# SCH_LED-CHASER_2025-11-11.net
KiCad netlist of a schematic drawn in EasyEDA
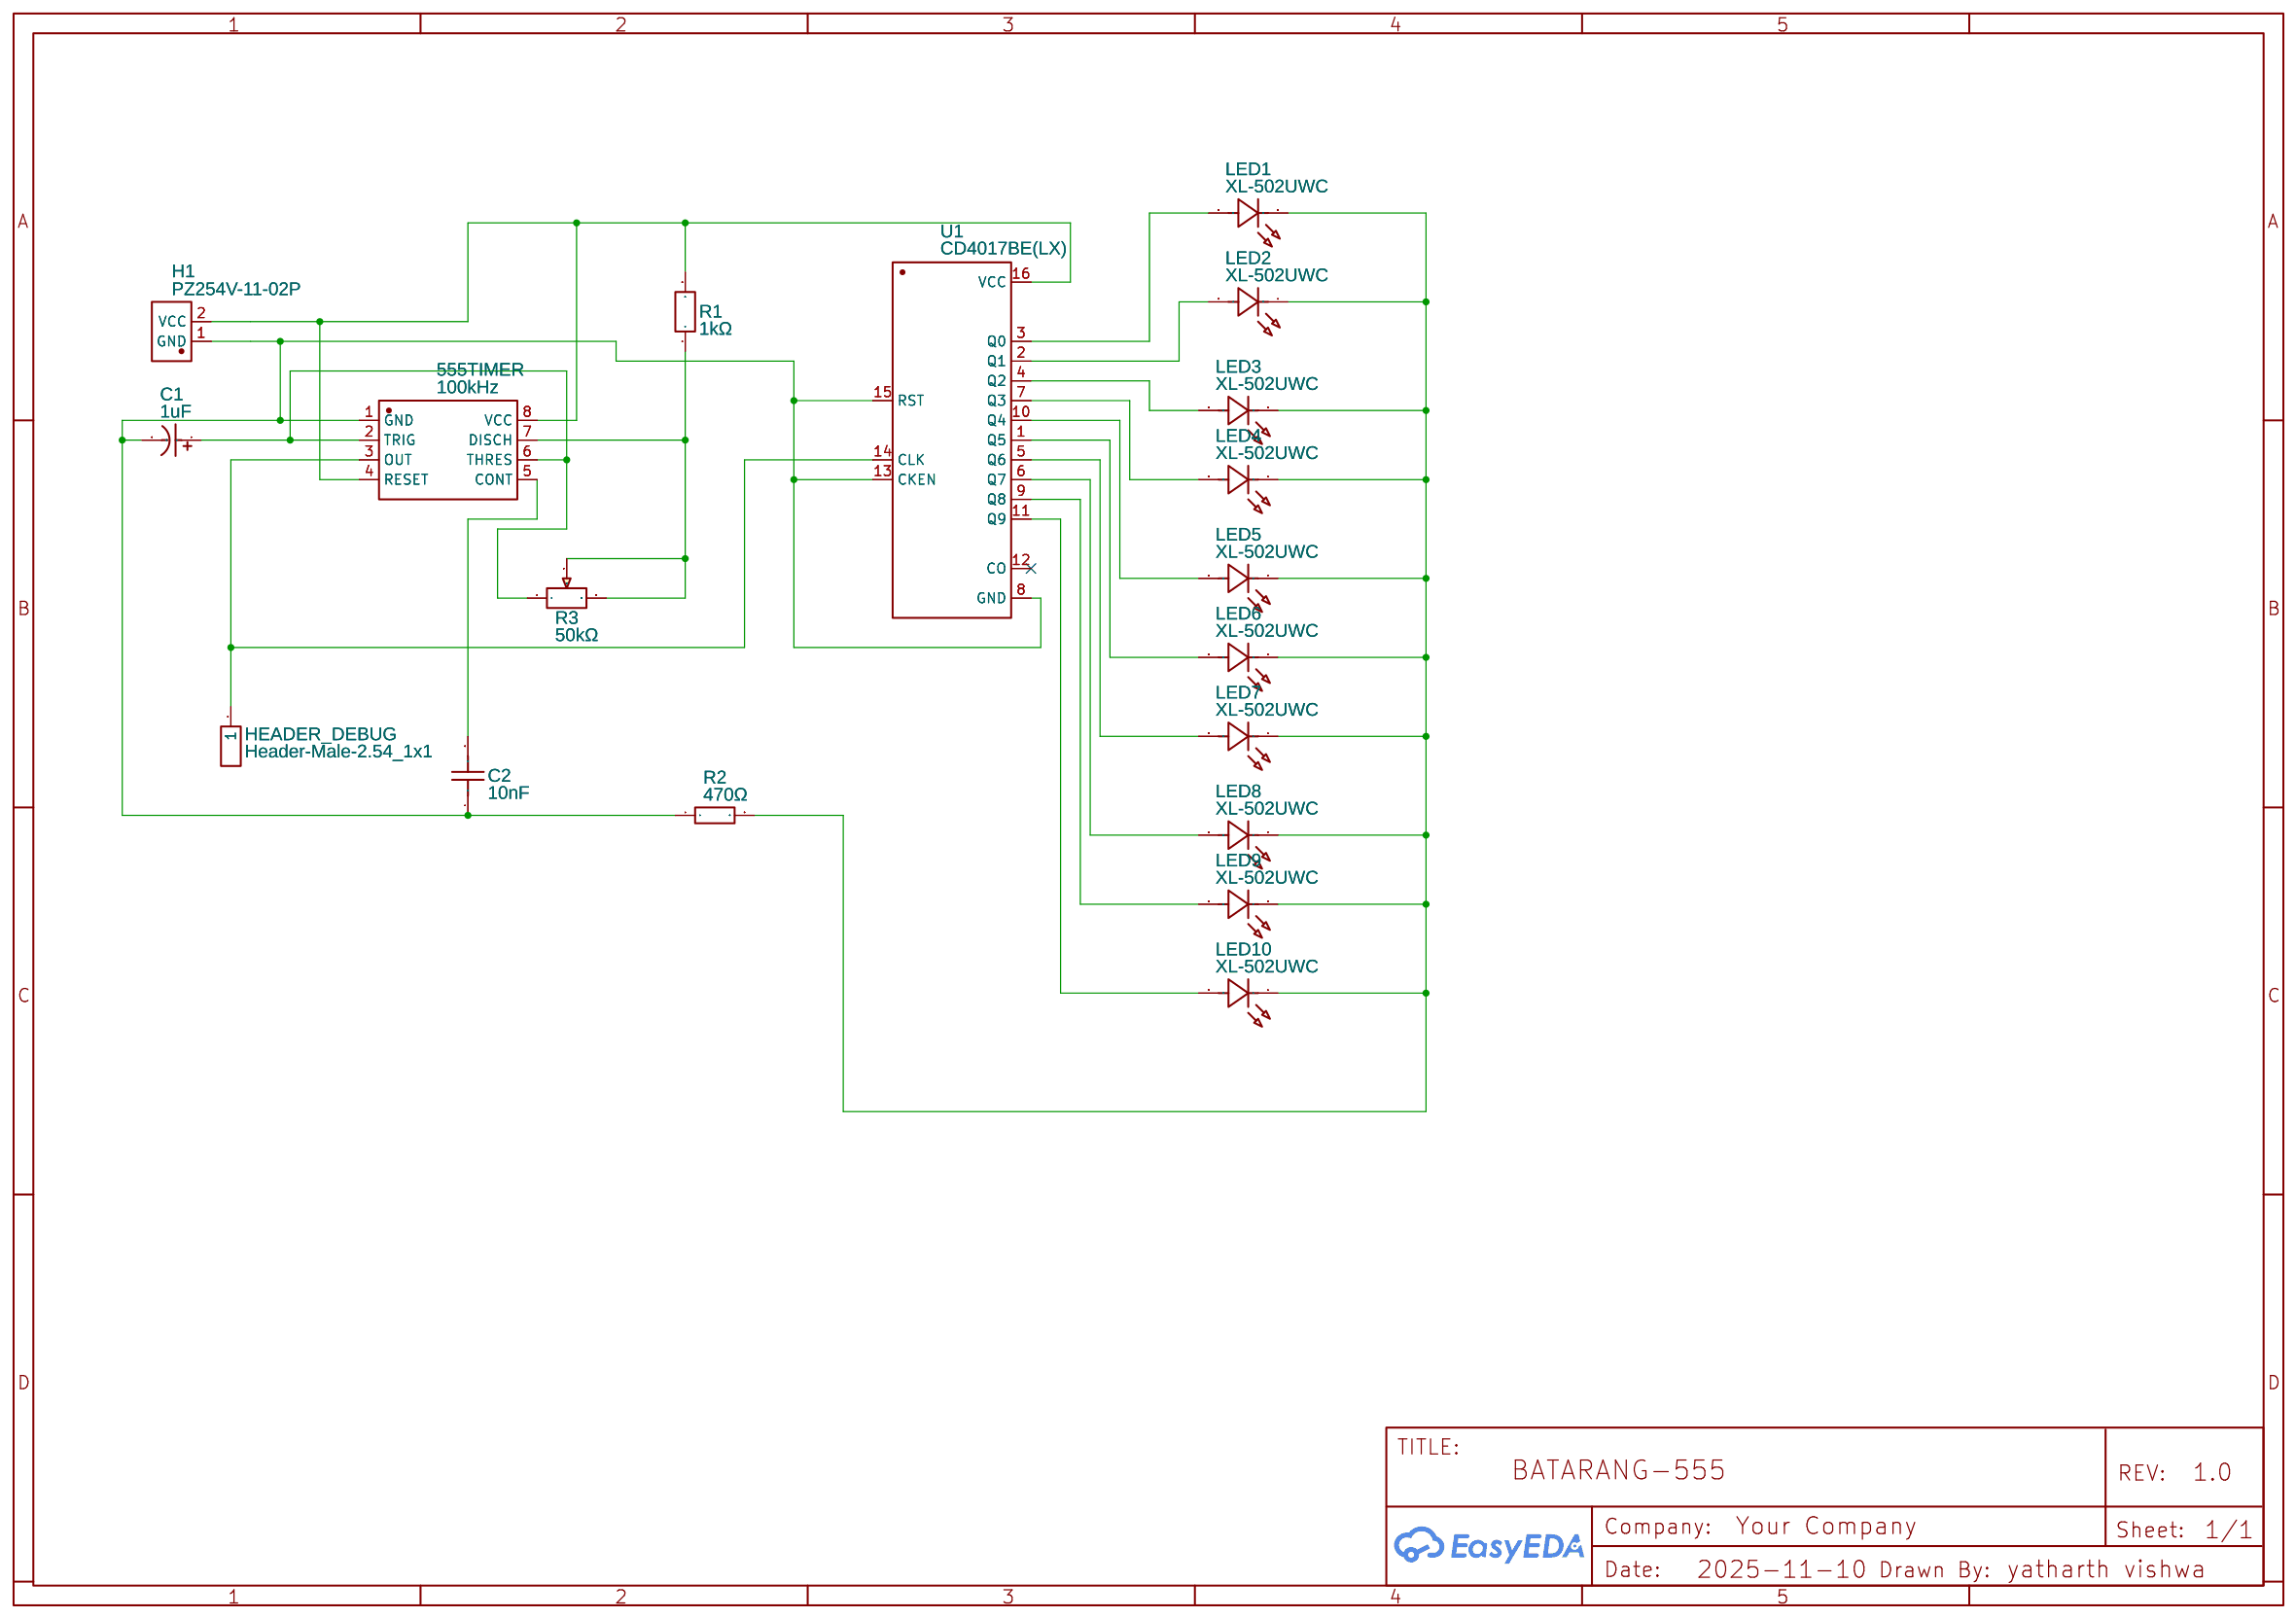
[diagram p0: schematic sheet]

(export (version "E")
  (design (tool "Eeschema 10.0.6"))
  (components
    (comp (ref "555TIMER")
      (value "100kHz")
      (fields (field (name "Manufacturer Part") "NE555P") (field (name "Manufacturer") "TI(德州仪器)"))
      (libsource (lib "") (part "NE555P"))
    )
    (comp (ref "C1")
      (value "1uF")
      (fields (field (name "Manufacturer Part") "KF010M050C110A") (field (name "Manufacturer") "CapXon(丰宾)"))
      (libsource (lib "") (part "KF010M050C110A"))
    )
    (comp (ref "C2")
      (value "10nF")
      (fields (field (name "Manufacturer Part") "N09F1B103MN0B0S0N0") (field (name "Manufacturer") "STE(松田)"))
      (libsource (lib "") (part "N09F1B103MN0B0S0N0"))
    )
    (comp (ref "H1")
      (value "PZ254V-11-02P")
      (fields (field (name "Manufacturer") "XFCN(兴飞)"))
      (libsource (lib "") (part "PZ254V-11-02P"))
    )
    (comp (ref "HEADER_DEBUG")
      (value "Header-Male-2.54_1x1")
      (fields (field (name "Manufacturer Part") "2.54-1*1P针") (field (name "Manufacturer") "BOOMELE(博穆精密)"))
      (libsource (lib "") (part "Header-Male-2.54_1x1"))
    )
    (comp (ref "LED1")
      (value "XL-502UWC")
      (fields (field (name "Manufacturer") "XINGLIGHT(成兴光)"))
      (libsource (lib "") (part "XL-502UWC"))
    )
    (comp (ref "LED2")
      (value "XL-502UWC")
      (fields (field (name "Manufacturer") "XINGLIGHT(成兴光)"))
      (libsource (lib "") (part "XL-502UWC"))
    )
    (comp (ref "LED3")
      (value "XL-502UWC")
      (fields (field (name "Manufacturer") "XINGLIGHT(成兴光)"))
      (libsource (lib "") (part "XL-502UWC"))
    )
    (comp (ref "LED4")
      (value "XL-502UWC")
      (fields (field (name "Manufacturer") "XINGLIGHT(成兴光)"))
      (libsource (lib "") (part "XL-502UWC"))
    )
    (comp (ref "LED5")
      (value "XL-502UWC")
      (fields (field (name "Manufacturer") "XINGLIGHT(成兴光)"))
      (libsource (lib "") (part "XL-502UWC"))
    )
    (comp (ref "LED6")
      (value "XL-502UWC")
      (fields (field (name "Manufacturer") "XINGLIGHT(成兴光)"))
      (libsource (lib "") (part "XL-502UWC"))
    )
    (comp (ref "LED7")
      (value "XL-502UWC")
      (fields (field (name "Manufacturer") "XINGLIGHT(成兴光)"))
      (libsource (lib "") (part "XL-502UWC"))
    )
    (comp (ref "LED8")
      (value "XL-502UWC")
      (fields (field (name "Manufacturer") "XINGLIGHT(成兴光)"))
      (libsource (lib "") (part "XL-502UWC"))
    )
    (comp (ref "LED9")
      (value "XL-502UWC")
      (fields (field (name "Manufacturer") "XINGLIGHT(成兴光)"))
      (libsource (lib "") (part "XL-502UWC"))
    )
    (comp (ref "LED10")
      (value "XL-502UWC")
      (fields (field (name "Manufacturer") "XINGLIGHT(成兴光)"))
      (libsource (lib "") (part "XL-502UWC"))
    )
    (comp (ref "R1")
      (value "1kΩ")
      (fields (field (name "Manufacturer Part") "MF1/4W-1KΩ±1%T52") (field (name "Manufacturer") "华星机电"))
      (libsource (lib "") (part "MF1/4W-1KΩ±1%T52"))
    )
    (comp (ref "R2")
      (value "470Ω")
      (fields
        (field (name "Manufacturer Part") "MFR0W4F4700A50")
        (field (name "Manufacturer") "UNI-ROYAL(厚声)")
      )
      (libsource (lib "") (part "MFR0W4F4700A50"))
    )
    (comp (ref "R3")
      (value "50kΩ")
      (fields (field (name "Manufacturer Part") "3296X-1-503") (field (name "Manufacturer") "BOCHEN(博晨)"))
      (libsource (lib "") (part "3296X-1-503_C118912"))
    )
    (comp (ref "U1")
      (value "CD4017BE(LX)")
      (fields (field (name "Manufacturer") "LX(灵星芯微)"))
      (libsource (lib "") (part "CD4017BE(LX)"))
    )
  )
  (nets
    (net (code "1") (name "Net-(555TIMER-CONT)") (class "Default")
      (node (ref "555TIMER") (pin "5") (pinfunction "CONT_5") (pintype "unspecified"))
      (node (ref "C2") (pin "2") (pinfunction "2_2") (pintype "unspecified"))
    )
    (net (code "2") (name "Net-(555TIMER-DISCH)") (class "Default")
      (node (ref "555TIMER") (pin "7") (pinfunction "DISCH_7") (pintype "unspecified"))
      (node (ref "R1") (pin "1") (pinfunction "1_1") (pintype "unspecified"))
      (node (ref "R3") (pin "2") (pinfunction "2_2") (pintype "input"))
      (node (ref "R3") (pin "3") (pinfunction "3_3") (pintype "input"))
    )
    (net (code "3") (name "Net-(555TIMER-GND)") (class "Default")
      (node (ref "555TIMER") (pin "1") (pinfunction "GND_1") (pintype "unspecified"))
      (node (ref "C1") (pin "2") (pinfunction "2_2") (pintype "input"))
      (node (ref "C2") (pin "1") (pinfunction "1_1") (pintype "unspecified"))
      (node (ref "H1") (pin "1") (pinfunction "GND_1") (pintype "unspecified"))
      (node (ref "R2") (pin "1") (pinfunction "1_1") (pintype "input"))
      (node (ref "U1") (pin "13") (pinfunction "CKEN_13") (pintype "unspecified"))
      (node (ref "U1") (pin "15") (pinfunction "RST_15") (pintype "unspecified"))
      (node (ref "U1") (pin "8") (pinfunction "GND_8") (pintype "unspecified"))
    )
    (net (code "4") (name "Net-(555TIMER-OUT)") (class "Default")
      (node (ref "555TIMER") (pin "3") (pinfunction "OUT_3") (pintype "unspecified"))
      (node (ref "HEADER_DEBUG") (pin "1") (pinfunction "1_1") (pintype "input"))
      (node (ref "U1") (pin "14") (pinfunction "CLK_14") (pintype "unspecified"))
    )
    (net (code "5") (name "Net-(555TIMER-RESET)") (class "Default")
      (node (ref "555TIMER") (pin "4") (pinfunction "RESET_4") (pintype "unspecified"))
      (node (ref "555TIMER") (pin "8") (pinfunction "VCC_8") (pintype "unspecified"))
      (node (ref "H1") (pin "2") (pinfunction "VCC_2") (pintype "unspecified"))
      (node (ref "R1") (pin "2") (pinfunction "2_2") (pintype "unspecified"))
      (node (ref "U1") (pin "16") (pinfunction "VCC_16") (pintype "unspecified"))
    )
    (net (code "6") (name "Net-(555TIMER-THRES)") (class "Default")
      (node (ref "555TIMER") (pin "2") (pinfunction "TRIG_2") (pintype "unspecified"))
      (node (ref "555TIMER") (pin "6") (pinfunction "THRES_6") (pintype "unspecified"))
      (node (ref "C1") (pin "1") (pinfunction "1_1") (pintype "input"))
      (node (ref "R3") (pin "1") (pinfunction "1_1") (pintype "input"))
    )
    (net (code "7") (name "Net-(LED1-A)") (class "Default")
      (node (ref "LED1") (pin "2") (pinfunction "A_2") (pintype "unspecified"))
      (node (ref "U1") (pin "3") (pinfunction "Q0_3") (pintype "unspecified"))
    )
    (net (code "8") (name "Net-(LED1-K)") (class "Default")
      (node (ref "LED1") (pin "1") (pinfunction "K_1") (pintype "unspecified"))
      (node (ref "LED10") (pin "1") (pinfunction "K_1") (pintype "unspecified"))
      (node (ref "LED2") (pin "1") (pinfunction "K_1") (pintype "unspecified"))
      (node (ref "LED3") (pin "1") (pinfunction "K_1") (pintype "unspecified"))
      (node (ref "LED4") (pin "1") (pinfunction "K_1") (pintype "unspecified"))
      (node (ref "LED5") (pin "1") (pinfunction "K_1") (pintype "unspecified"))
      (node (ref "LED6") (pin "1") (pinfunction "K_1") (pintype "unspecified"))
      (node (ref "LED7") (pin "1") (pinfunction "K_1") (pintype "unspecified"))
      (node (ref "LED8") (pin "1") (pinfunction "K_1") (pintype "unspecified"))
      (node (ref "LED9") (pin "1") (pinfunction "K_1") (pintype "unspecified"))
      (node (ref "R2") (pin "2") (pinfunction "2_2") (pintype "input"))
    )
    (net (code "9") (name "Net-(LED2-A)") (class "Default")
      (node (ref "LED2") (pin "2") (pinfunction "A_2") (pintype "unspecified"))
      (node (ref "U1") (pin "2") (pinfunction "Q1_2") (pintype "unspecified"))
    )
    (net (code "10") (name "Net-(LED3-A)") (class "Default")
      (node (ref "LED3") (pin "2") (pinfunction "A_2") (pintype "unspecified"))
      (node (ref "U1") (pin "4") (pinfunction "Q2_4") (pintype "unspecified"))
    )
    (net (code "11") (name "Net-(LED4-A)") (class "Default")
      (node (ref "LED4") (pin "2") (pinfunction "A_2") (pintype "unspecified"))
      (node (ref "U1") (pin "7") (pinfunction "Q3_7") (pintype "unspecified"))
    )
    (net (code "12") (name "Net-(LED5-A)") (class "Default")
      (node (ref "LED5") (pin "2") (pinfunction "A_2") (pintype "unspecified"))
      (node (ref "U1") (pin "10") (pinfunction "Q4_10") (pintype "unspecified"))
    )
    (net (code "13") (name "Net-(LED6-A)") (class "Default")
      (node (ref "LED6") (pin "2") (pinfunction "A_2") (pintype "unspecified"))
      (node (ref "U1") (pin "1") (pinfunction "Q5_1") (pintype "unspecified"))
    )
    (net (code "14") (name "Net-(LED7-A)") (class "Default")
      (node (ref "LED7") (pin "2") (pinfunction "A_2") (pintype "unspecified"))
      (node (ref "U1") (pin "5") (pinfunction "Q6_5") (pintype "unspecified"))
    )
    (net (code "15") (name "Net-(LED8-A)") (class "Default")
      (node (ref "LED8") (pin "2") (pinfunction "A_2") (pintype "unspecified"))
      (node (ref "U1") (pin "6") (pinfunction "Q7_6") (pintype "unspecified"))
    )
    (net (code "16") (name "Net-(LED9-A)") (class "Default")
      (node (ref "LED9") (pin "2") (pinfunction "A_2") (pintype "unspecified"))
      (node (ref "U1") (pin "9") (pinfunction "Q8_9") (pintype "unspecified"))
    )
    (net (code "17") (name "Net-(LED10-A)") (class "Default")
      (node (ref "LED10") (pin "2") (pinfunction "A_2") (pintype "unspecified"))
      (node (ref "U1") (pin "11") (pinfunction "Q9_11") (pintype "unspecified"))
    )
    (net (code "18") (name "unconnected-(U1-CO-Pad12)") (class "Default")
      (node (ref "U1") (pin "12") (pinfunction "CO_12") (pintype "unspecified+no_connect"))
    )
  )
)
